# Optical_Fiber.net
KiCad netlist of a schematic drawn in Altium Designer
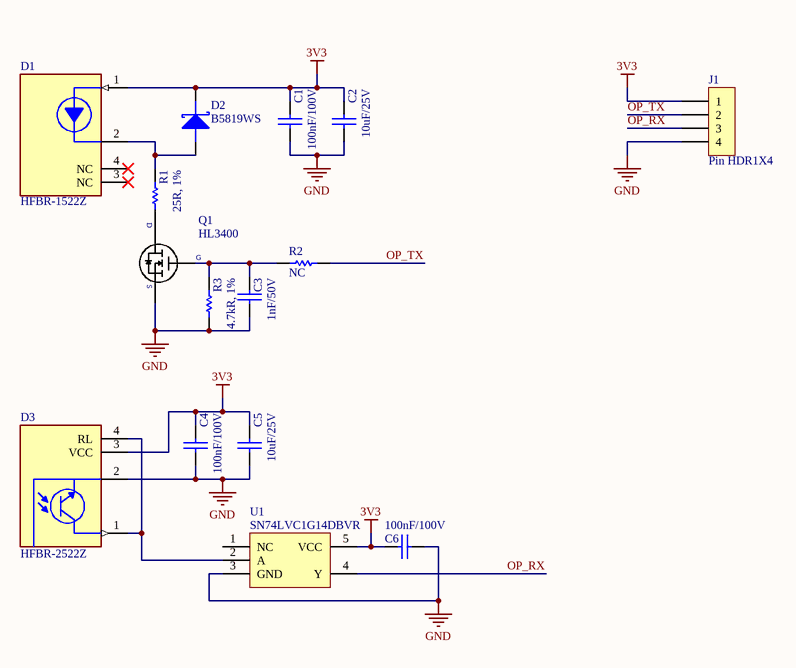
[diagram p0: Optical_Fiber.SchDoc]

(export (version "E")
  (design (tool "Eeschema 10.0.6"))
  (components
    (comp (ref "C1")
      (value "100nF/100V")
      (footprint "0603C")
      (description "CC0603KRX7R9BB104")
      (libsource (lib "MyLib") (part "CAP"))
    )
    (comp (ref "C2")
      (value "10uF/25V")
      (footprint "0603C")
      (description "CC0603MRX5R8BB106")
      (libsource (lib "MyLib") (part "CAP"))
    )
    (comp (ref "C3")
      (value "1nF/50V")
      (footprint "0603C")
      (description "CC0603KRX7R9BB102")
      (libsource (lib "MyLib") (part "CAP"))
    )
    (comp (ref "C4")
      (value "100nF/100V")
      (footprint "0603C")
      (description "CC0603KRX7R9BB104")
      (libsource (lib "MyLib") (part "CAP"))
    )
    (comp (ref "C5")
      (value "10uF/25V")
      (footprint "0603C")
      (description "CC0603MRX5R8BB106")
      (libsource (lib "MyLib") (part "CAP"))
    )
    (comp (ref "C6")
      (value "100nF/100V")
      (footprint "0603C")
      (description "CC0603KRX7R9BB104")
      (libsource (lib "MyLib") (part "CAP"))
    )
    (comp (ref "D1")
      (value "HFBR-1522Z")
      (footprint "HFBR_1521Z")
      (description "Versatile Link Fiber-Optic Connection")
      (fields (field (name "MF") "Broadcom Limited") (field (name "MP") "HFBR-2521Z"))
      (libsource (lib "CustomizedLib") (part "HFBR-1521Z"))
    )
    (comp (ref "D2")
      (value "B5819WS")
      (footprint "SOD-123")
      (libsource (lib "MyLib") (part "DIODE SCHOTTKY"))
    )
    (comp (ref "D3")
      (value "HFBR-2522Z")
      (footprint "HFBR_2521Z")
      (description "Versatile Link Fiber-Optic Connection")
      (fields (field (name "MF") "Broadcom Limited") (field (name "MP") "HFBR-2521Z"))
      (libsource (lib "CustomizedLib") (part "HFBR-2521Z"))
    )
    (comp (ref "J1")
      (value "Pin HDR1X4")
      (footprint "Pin HDR1X4/2.54mm-W")
      (libsource (lib "MyLib") (part "Pin HDR1X4"))
    )
    (comp (ref "Q1") (value "HL3400") (footprint "SOT23-3") (libsource (lib "CustomizedLib") (part "NMOS")))
    (comp (ref "R1")
      (value "25R, 1%")
      (footprint "0603R")
      (description "RP0603BRD0725RL")
      (libsource (lib "MyLib") (part "RES"))
    )
    (comp (ref "R2") (value "NC") (footprint "0603R") (libsource (lib "MyLib") (part "RES")))
    (comp (ref "R3")
      (value "4.7kR, 1%")
      (footprint "0603R")
      (description "RC0603FR-074K7L")
      (libsource (lib "MyLib") (part "RES"))
    )
    (comp (ref "U1")
      (value "SN74LVC1G14DBVR")
      (footprint "SOT23-5")
      (description "Y=A\\")
      (libsource (lib "CustomizedLib") (part "SN74LVC1G14DBVR"))
    )
  )
  (nets
    (net (code "1") (name "/OP_RX") (class "Default")
      (node (ref "J1") (pin "3") (pinfunction "3_3") (pintype "passive"))
      (node (ref "U1") (pin "4") (pinfunction "Y_4") (pintype "passive"))
    )
    (net (code "2") (name "/OP_TX") (class "Default")
      (node (ref "J1") (pin "2") (pinfunction "2_2") (pintype "passive"))
      (node (ref "R2") (pin "1") (pinfunction "1_1") (pintype "passive"))
    )
    (net (code "3") (name "3V3") (class "Default")
      (node (ref "C1") (pin "1") (pinfunction "1_1") (pintype "passive"))
      (node (ref "C2") (pin "1") (pinfunction "1_1") (pintype "passive"))
      (node (ref "C4") (pin "1") (pinfunction "1_1") (pintype "passive"))
      (node (ref "C5") (pin "1") (pinfunction "1_1") (pintype "passive"))
      (node (ref "C6") (pin "1") (pinfunction "1_1") (pintype "passive"))
      (node (ref "D1") (pin "1") (pinfunction "VO_1") (pintype "input"))
      (node (ref "D2") (pin "K") (pinfunction "K_K") (pintype "passive"))
      (node (ref "D3") (pin "3") (pinfunction "VCC_3") (pintype "power_in"))
      (node (ref "J1") (pin "1") (pinfunction "1_1") (pintype "passive"))
      (node (ref "U1") (pin "5") (pinfunction "VCC_5") (pintype "passive"))
    )
    (net (code "4") (name "GND") (class "Default")
      (node (ref "C1") (pin "2") (pinfunction "2_2") (pintype "passive"))
      (node (ref "C2") (pin "2") (pinfunction "2_2") (pintype "passive"))
      (node (ref "C3") (pin "1") (pinfunction "1_1") (pintype "passive"))
      (node (ref "C4") (pin "2") (pinfunction "2_2") (pintype "passive"))
      (node (ref "C5") (pin "2") (pinfunction "2_2") (pintype "passive"))
      (node (ref "C6") (pin "2") (pinfunction "2_2") (pintype "passive"))
      (node (ref "D3") (pin "2") (pinfunction "GROUND_2") (pintype "power_in"))
      (node (ref "J1") (pin "4") (pinfunction "4_4") (pintype "passive"))
      (node (ref "Q1") (pin "2") (pinfunction "2_2") (pintype "passive"))
      (node (ref "R3") (pin "1") (pinfunction "1_1") (pintype "passive"))
      (node (ref "U1") (pin "3") (pinfunction "GND_3") (pintype "passive"))
    )
    (net (code "5") (name "Net-(C3-Pad2)") (class "Default")
      (node (ref "C3") (pin "2") (pinfunction "2_2") (pintype "passive"))
      (node (ref "Q1") (pin "1") (pinfunction "1_1") (pintype "passive"))
      (node (ref "R2") (pin "2") (pinfunction "2_2") (pintype "passive"))
      (node (ref "R3") (pin "2") (pinfunction "2_2") (pintype "passive"))
    )
    (net (code "6") (name "Net-(D1-GROUND)") (class "Default")
      (node (ref "D1") (pin "2") (pinfunction "GROUND_2") (pintype "power_in"))
      (node (ref "D2") (pin "A") (pinfunction "A_A") (pintype "passive"))
      (node (ref "R1") (pin "1") (pinfunction "1_1") (pintype "passive"))
    )
    (net (code "7") (name "Net-(D3-RL)") (class "Default")
      (node (ref "D3") (pin "1") (pinfunction "VO_1") (pintype "output"))
      (node (ref "D3") (pin "4") (pinfunction "RL_4") (pintype "passive"))
      (node (ref "U1") (pin "2") (pinfunction "A_2") (pintype "passive"))
    )
    (net (code "8") (name "Net-(Q1-Pad3)") (class "Default")
      (node (ref "Q1") (pin "3") (pinfunction "3_3") (pintype "passive"))
      (node (ref "R1") (pin "2") (pinfunction "2_2") (pintype "passive"))
    )
    (net (code "9") (name "unconnected-(D1-NC-Pad3)") (class "Default")
      (node (ref "D1") (pin "3") (pinfunction "NC_3") (pintype "power_in+no_connect"))
    )
    (net (code "10") (name "unconnected-(D1-NC-Pad4)") (class "Default")
      (node (ref "D1") (pin "4") (pinfunction "NC_4") (pintype "passive+no_connect"))
    )
    (net (code "11") (name "unconnected-(U1-NC-Pad1)") (class "Default")
      (node (ref "U1") (pin "1") (pinfunction "NC_1") (pintype "passive"))
    )
  )
)
